# clock_using_555_1_1.net
KiCad netlist of a schematic drawn in EAGLE
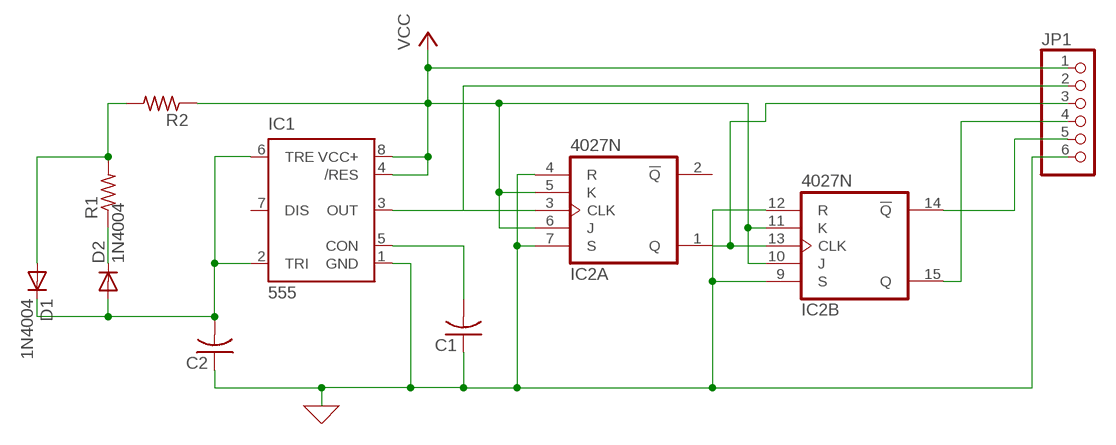
[diagram p0: schematic, sheet 1]

(export (version "E")
  (design (tool "Eeschema 10.0.6"))
  (components
    (comp (ref "C1")
      (value "C-US025-025X050")
      (footprint "eagle-import:C025-025X050")
      (libsource (lib "eagle-import") (part "C-US025-025X050"))
    )
    (comp (ref "C2")
      (value "C-US025-025X050")
      (footprint "eagle-import:C025-025X050")
      (libsource (lib "eagle-import") (part "C-US025-025X050"))
    )
    (comp (ref "D1")
      (value "1N4004")
      (footprint "eagle-import:DO41-10")
      (libsource (lib "eagle-import") (part "1N4004"))
    )
    (comp (ref "D2")
      (value "1N4004")
      (footprint "eagle-import:DO41-10")
      (libsource (lib "eagle-import") (part "1N4004"))
    )
    (comp (ref "IC1")
      (value "555")
      (footprint "eagle-import:DIP08")
      (libsource (lib "eagle-import") (part "555P"))
    )
    (comp (ref "IC2")
      (value "4027N")
      (footprint "eagle-import:DIL16")
      (libsource (lib "eagle-import") (part "4027N"))
    )
    (comp (ref "JP1")
      (value "PINHD-1X6CB")
      (footprint "eagle-import:1X06-CLEANBIG")
      (libsource (lib "eagle-import") (part "PINHD-1X6CB"))
    )
    (comp (ref "R1")
      (value "R-US_0204/5")
      (footprint "eagle-import:0204_5")
      (libsource (lib "eagle-import") (part "R-US_0204/5"))
    )
    (comp (ref "R2")
      (value "R-US_0204/5")
      (footprint "eagle-import:0204_5")
      (libsource (lib "eagle-import") (part "R-US_0204/5"))
    )
  )
  (nets
    (net (code "1") (name "GND") (class "Default")
      (node (ref "C1") (pin "1") (pinfunction "1_1") (pintype "passive"))
      (node (ref "C2") (pin "1") (pinfunction "1_1") (pintype "passive"))
      (node (ref "IC1") (pin "1") (pinfunction "GND_1") (pintype "power_in"))
      (node (ref "IC2") (pin "12") (pinfunction "R_12") (pintype "input"))
      (node (ref "IC2") (pin "4") (pinfunction "R_4") (pintype "input"))
      (node (ref "IC2") (pin "7") (pinfunction "S_7") (pintype "input"))
      (node (ref "IC2") (pin "9") (pinfunction "S_9") (pintype "input"))
      (node (ref "JP1") (pin "6") (pinfunction "6_6") (pintype "passive"))
    )
    (net (code "2") (name "Net-(D1-PadA)") (class "Default")
      (node (ref "D1") (pin "A") (pinfunction "A_A") (pintype "passive"))
      (node (ref "R1") (pin "2") (pinfunction "2_2") (pintype "passive"))
      (node (ref "R2") (pin "2") (pinfunction "2_2") (pintype "passive"))
    )
    (net (code "3") (name "Net-(D2-PadC)") (class "Default")
      (node (ref "D2") (pin "C") (pinfunction "C_C") (pintype "passive"))
      (node (ref "R1") (pin "1") (pinfunction "1_1") (pintype "passive"))
    )
    (net (code "4") (name "Net-(IC1-CON)") (class "Default")
      (node (ref "C1") (pin "2") (pinfunction "2_2") (pintype "passive"))
      (node (ref "IC1") (pin "5") (pinfunction "CON_5") (pintype "input"))
    )
    (net (code "5") (name "Net-(IC1-OUT)") (class "Default")
      (node (ref "IC1") (pin "3") (pinfunction "OUT_3") (pintype "output"))
      (node (ref "IC2") (pin "3") (pinfunction "CLK_3") (pintype "input"))
      (node (ref "JP1") (pin "2") (pinfunction "2_2") (pintype "passive"))
    )
    (net (code "6") (name "Net-(IC1-TRE)") (class "Default")
      (node (ref "C2") (pin "2") (pinfunction "2_2") (pintype "passive"))
      (node (ref "D1") (pin "C") (pinfunction "C_C") (pintype "passive"))
      (node (ref "D2") (pin "A") (pinfunction "A_A") (pintype "passive"))
      (node (ref "IC1") (pin "2") (pinfunction "TRI_2") (pintype "input"))
      (node (ref "IC1") (pin "6") (pinfunction "TRE_6") (pintype "input"))
    )
    (net (code "7") (name "Net-(IC2A-Q)") (class "Default")
      (node (ref "IC2") (pin "1") (pinfunction "Q_1") (pintype "output"))
      (node (ref "IC2") (pin "13") (pinfunction "CLK_13") (pintype "input"))
      (node (ref "JP1") (pin "3") (pinfunction "3_3") (pintype "passive"))
    )
    (net (code "8") (name "Net-(IC2B-Q)") (class "Default")
      (node (ref "IC2") (pin "15") (pinfunction "Q_15") (pintype "output"))
      (node (ref "JP1") (pin "4") (pinfunction "4_4") (pintype "passive"))
    )
    (net (code "9") (name "Net-(IC2B-~{Q})") (class "Default")
      (node (ref "IC2") (pin "14") (pinfunction "~{Q}_14") (pintype "output"))
      (node (ref "JP1") (pin "5") (pinfunction "5_5") (pintype "passive"))
    )
    (net (code "10") (name "VCC") (class "Default")
      (node (ref "IC1") (pin "4") (pinfunction "/RES_4") (pintype "input"))
      (node (ref "IC1") (pin "8") (pinfunction "VCC+_8") (pintype "power_in"))
      (node (ref "IC2") (pin "10") (pinfunction "J_10") (pintype "input"))
      (node (ref "IC2") (pin "11") (pinfunction "K_11") (pintype "input"))
      (node (ref "IC2") (pin "5") (pinfunction "K_5") (pintype "input"))
      (node (ref "IC2") (pin "6") (pinfunction "J_6") (pintype "input"))
      (node (ref "JP1") (pin "1") (pinfunction "1_1") (pintype "passive"))
      (node (ref "R2") (pin "1") (pinfunction "1_1") (pintype "passive"))
    )
    (net (code "11") (name "unconnected-(IC1-DIS-Pad7)") (class "Default")
      (node (ref "IC1") (pin "7") (pinfunction "DIS_7") (pintype "input"))
    )
    (net (code "12") (name "unconnected-(IC2A-~{Q}-Pad2)") (class "Default")
      (node (ref "IC2") (pin "2") (pinfunction "~{Q}_2") (pintype "output"))
    )
  )
)
